# Nuio_LeftKeyboard_Rev_E_2_MCU.net
KiCad netlist of a schematic drawn in Altium Designer
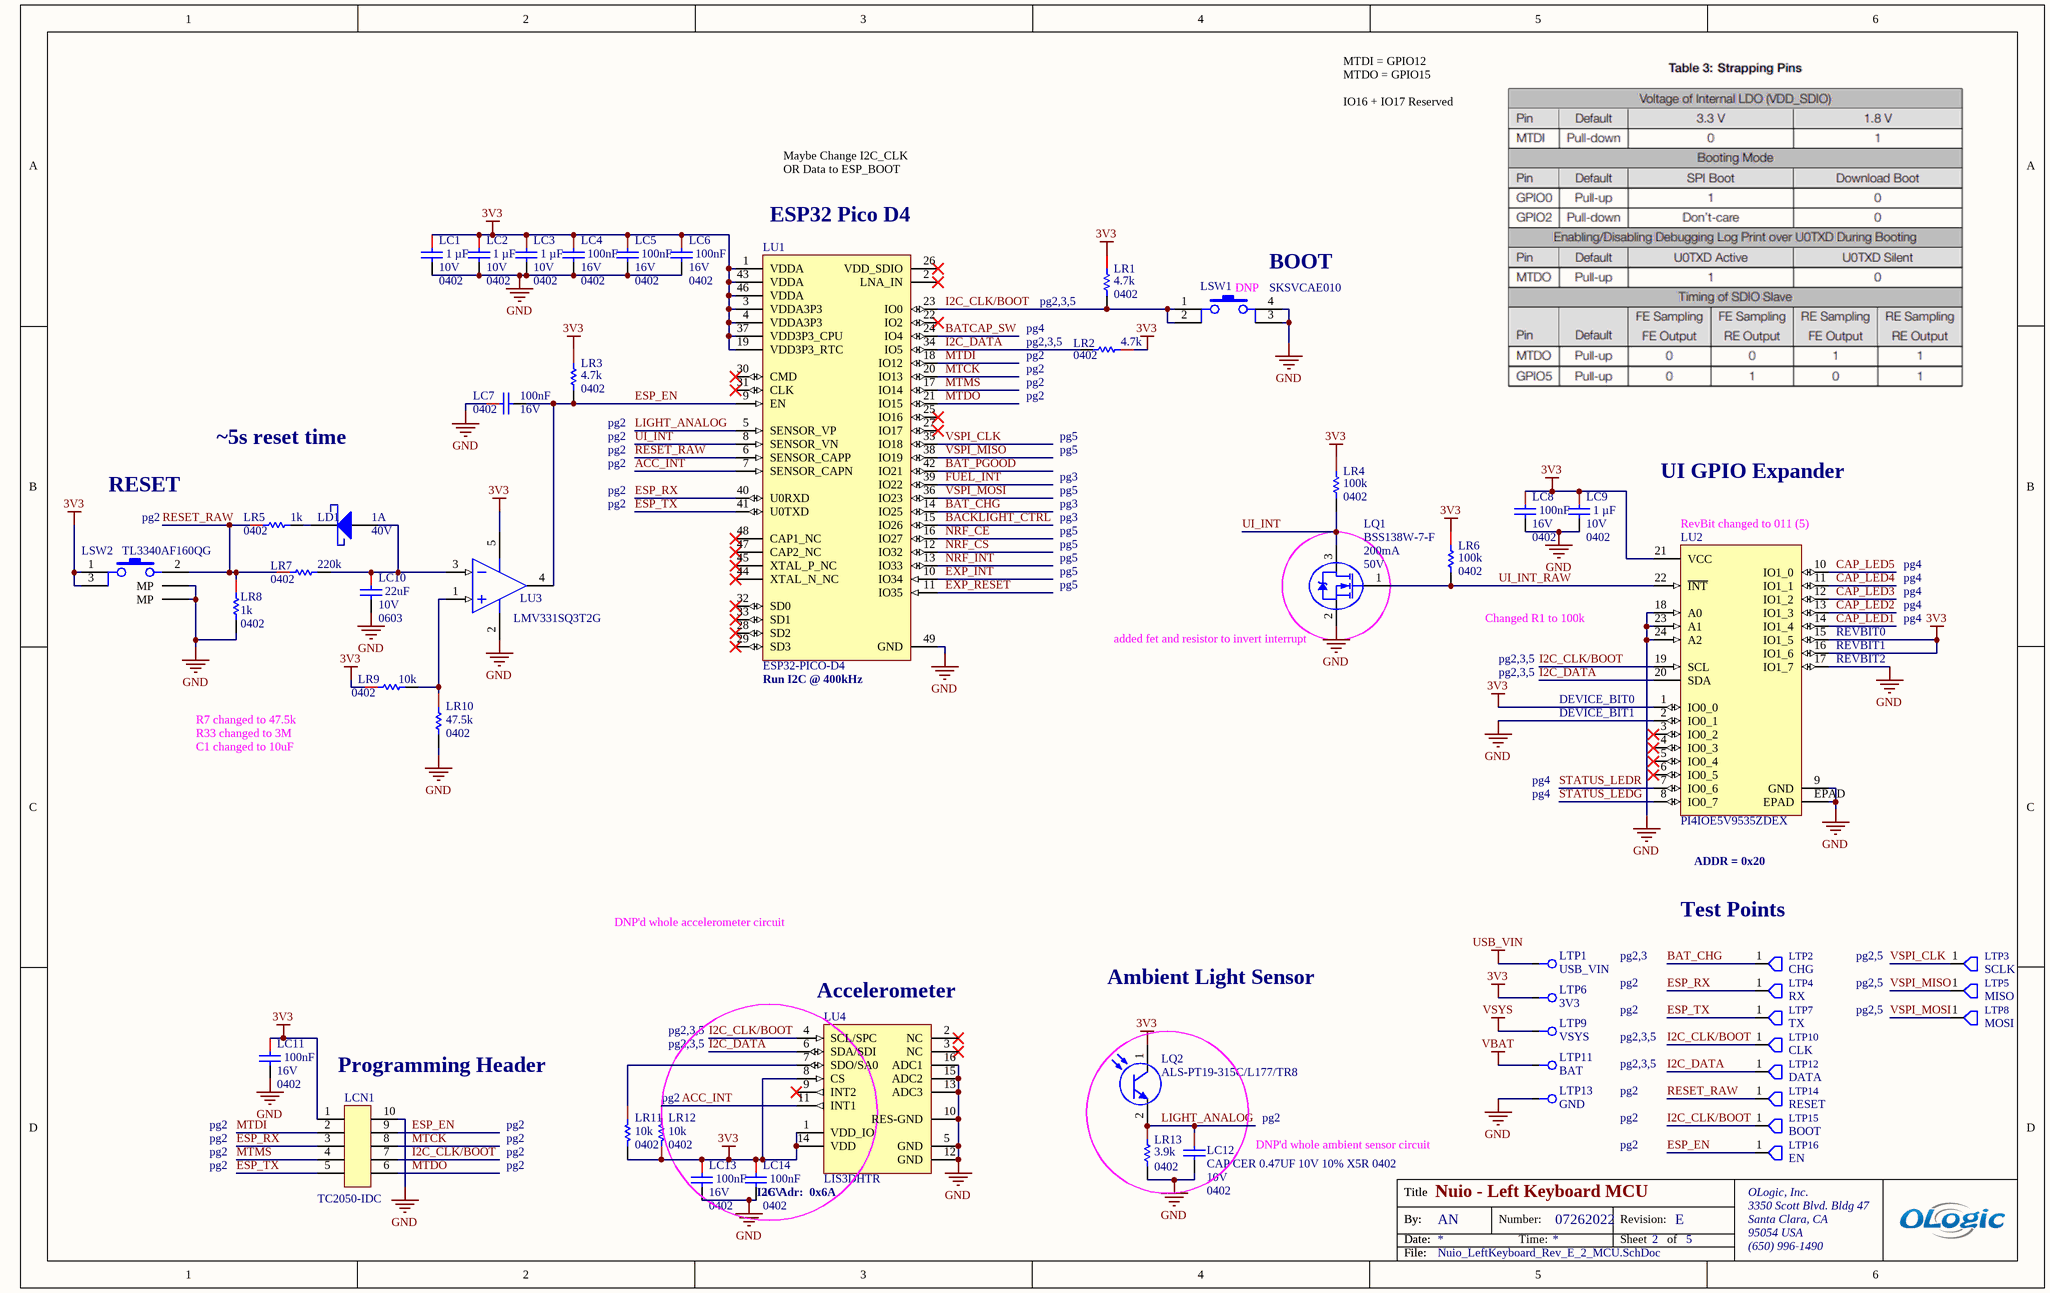
[diagram p0: Nuio_LeftKeyboard_Rev_E_2_MCU.SchDoc]

(export (version "E")
  (design (tool "Eeschema 10.0.6"))
  (components
    (comp (ref "LC1")
      (value "CAP CER 1UF 10V X5R 0402")
      (footprint "CAPC0402(1005)_L")
      (description "±20% 10V Ceramic Capacitor X5R 0402 (1005 Metric)")
      (fields
        (field (name "PACKAGE (IMPERIAL)") "0402")
        (field (name "VOLTAGE (RATED)") "10V")
        (field (name "CAPACITANCE") "1 µF")
        (field (name "MANUFACTURER PART NUMBER") "CC0402MRX5R6BB105")
        (field (name "TOLERANCE") "±20%")
      )
      (libsource (lib "OLogic Nexus Vault") (part "OL_Capacitor"))
    )
    (comp (ref "LC2")
      (value "CAP CER 1UF 10V X5R 0402")
      (footprint "CAPC0402(1005)_L")
      (description "±20% 10V Ceramic Capacitor X5R 0402 (1005 Metric)")
      (fields
        (field (name "PACKAGE (IMPERIAL)") "0402")
        (field (name "VOLTAGE (RATED)") "10V")
        (field (name "CAPACITANCE") "1 µF")
        (field (name "MANUFACTURER PART NUMBER") "CC0402MRX5R6BB105")
        (field (name "TOLERANCE") "±20%")
      )
      (libsource (lib "OLogic Nexus Vault") (part "OL_Capacitor"))
    )
    (comp (ref "LC3")
      (value "CAP CER 1UF 10V X5R 0402")
      (footprint "CAPC0402(1005)_L")
      (description "±20% 10V Ceramic Capacitor X5R 0402 (1005 Metric)")
      (fields
        (field (name "PACKAGE (IMPERIAL)") "0402")
        (field (name "VOLTAGE (RATED)") "10V")
        (field (name "CAPACITANCE") "1 µF")
        (field (name "MANUFACTURER PART NUMBER") "CC0402MRX5R6BB105")
        (field (name "TOLERANCE") "±20%")
      )
      (libsource (lib "OLogic Nexus Vault") (part "OL_Capacitor"))
    )
    (comp (ref "LC4")
      (value "CAP CER 0.1UF 16V X5R 0402")
      (footprint "CAPC0402(1005)_L")
      (description "±10% 16V Ceramic Capacitor X5R 0402 (1005 Metric)")
      (fields
        (field (name "PACKAGE (IMPERIAL)") "0402")
        (field (name "VOLTAGE (RATED)") "16V")
        (field (name "CAPACITANCE") "100nF")
        (field (name "MANUFACTURER") "Taiyo Yuden")
        (field (name "MANUFACTURER PART NUMBER") "EMK105BJ104KV-F")
      )
      (libsource (lib "OLogic Nexus Vault") (part "OL_Capacitor"))
    )
    (comp (ref "LC5")
      (value "CAP CER 0.1UF 16V X5R 0402")
      (footprint "CAPC0402(1005)_L")
      (description "±10% 16V Ceramic Capacitor X5R 0402 (1005 Metric)")
      (fields
        (field (name "PACKAGE (IMPERIAL)") "0402")
        (field (name "VOLTAGE (RATED)") "16V")
        (field (name "CAPACITANCE") "100nF")
        (field (name "MANUFACTURER") "Taiyo Yuden")
        (field (name "MANUFACTURER PART NUMBER") "EMK105BJ104KV-F")
      )
      (libsource (lib "OLogic Nexus Vault") (part "OL_Capacitor"))
    )
    (comp (ref "LC6")
      (value "CAP CER 0.1UF 16V X5R 0402")
      (footprint "CAPC0402(1005)_L")
      (description "±10% 16V Ceramic Capacitor X5R 0402 (1005 Metric)")
      (fields
        (field (name "PACKAGE (IMPERIAL)") "0402")
        (field (name "VOLTAGE (RATED)") "16V")
        (field (name "CAPACITANCE") "100nF")
        (field (name "MANUFACTURER") "Taiyo Yuden")
        (field (name "MANUFACTURER PART NUMBER") "EMK105BJ104KV-F")
      )
      (libsource (lib "OLogic Nexus Vault") (part "OL_Capacitor"))
    )
    (comp (ref "LC7")
      (value "CAP CER 0.1UF 16V X5R 0402")
      (footprint "CAPC0402(1005)_L")
      (description "±10% 16V Ceramic Capacitor X5R 0402 (1005 Metric)")
      (fields
        (field (name "PACKAGE (IMPERIAL)") "0402")
        (field (name "VOLTAGE (RATED)") "16V")
        (field (name "CAPACITANCE") "100nF")
        (field (name "MANUFACTURER") "Taiyo Yuden")
        (field (name "MANUFACTURER PART NUMBER") "EMK105BJ104KV-F")
      )
      (libsource (lib "OLogic Nexus Vault") (part "OL_Capacitor"))
    )
    (comp (ref "LC8")
      (value "CAP CER 0.1UF 16V X5R 0402")
      (footprint "CAPC0402(1005)_L")
      (description "±10% 16V Ceramic Capacitor X5R 0402 (1005 Metric)")
      (fields
        (field (name "PACKAGE (IMPERIAL)") "0402")
        (field (name "VOLTAGE (RATED)") "16V")
        (field (name "CAPACITANCE") "100nF")
        (field (name "MANUFACTURER") "Taiyo Yuden")
        (field (name "MANUFACTURER PART NUMBER") "EMK105BJ104KV-F")
      )
      (libsource (lib "OLogic Nexus Vault") (part "OL_Capacitor"))
    )
    (comp (ref "LC9")
      (value "CAP CER 1UF 10V X5R 0402")
      (footprint "CAPC0402(1005)_L")
      (description "±20% 10V Ceramic Capacitor X5R 0402 (1005 Metric)")
      (fields
        (field (name "PACKAGE (IMPERIAL)") "0402")
        (field (name "VOLTAGE (RATED)") "10V")
        (field (name "CAPACITANCE") "1 µF")
        (field (name "MANUFACTURER PART NUMBER") "CC0402MRX5R6BB105")
        (field (name "TOLERANCE") "±20%")
      )
      (libsource (lib "OLogic Nexus Vault") (part "OL_Capacitor"))
    )
    (comp (ref "LC10")
      (value "22uF")
      (footprint "CAPC0603(1608)_L")
      (description "CAP CER 22UF 10V 20% 0603")
      (fields
        (field (name "VOLTAGE RATING (DC)") "10V")
        (field (name "CASE CODE (IMPERIAL)") "0603")
        (field (name "TOLERANCE") "20%")
      )
      (libsource (lib "OLogic Nexus Vault") (part "=Capacitance"))
    )
    (comp (ref "LC11")
      (value "CAP CER 0.1UF 16V X5R 0402")
      (footprint "CAPC0402(1005)_L")
      (description "±10% 16V Ceramic Capacitor X5R 0402 (1005 Metric)")
      (fields
        (field (name "PACKAGE (IMPERIAL)") "0402")
        (field (name "VOLTAGE (RATED)") "16V")
        (field (name "CAPACITANCE") "100nF")
        (field (name "MANUFACTURER") "Taiyo Yuden")
        (field (name "MANUFACTURER PART NUMBER") "EMK105BJ104KV-F")
      )
      (libsource (lib "OLogic Nexus Vault") (part "OL_Capacitor"))
    )
    (comp (ref "LC12")
      (value "CAP CER 0.47UF 10V 10% X5R 0402")
      (footprint "CAPC0402(1005)_L")
      (description "0.47 µF ±10% 10V Ceramic Capacitor X7S 0402 (1005 Metric)")
      (fields
        (field (name "VOLTAGE (RATED)") "10V")
        (field (name "PACKAGE (IMPERIAL)") "0402")
        (field (name "TOLERANCE") "10%")
      )
      (libsource (lib "OLogic Nexus Vault") (part "OL_Capacitor"))
    )
    (comp (ref "LC13")
      (value "CAP CER 0.1UF 16V X5R 0402")
      (footprint "CAPC0402(1005)_L")
      (description "±10% 16V Ceramic Capacitor X5R 0402 (1005 Metric)")
      (fields
        (field (name "PACKAGE (IMPERIAL)") "0402")
        (field (name "VOLTAGE (RATED)") "16V")
        (field (name "CAPACITANCE") "100nF")
        (field (name "MANUFACTURER") "Taiyo Yuden")
        (field (name "MANUFACTURER PART NUMBER") "EMK105BJ104KV-F")
      )
      (libsource (lib "OLogic Nexus Vault") (part "OL_Capacitor"))
    )
    (comp (ref "LC14")
      (value "CAP CER 0.1UF 16V X5R 0402")
      (footprint "CAPC0402(1005)_L")
      (description "±10% 16V Ceramic Capacitor X5R 0402 (1005 Metric)")
      (fields
        (field (name "PACKAGE (IMPERIAL)") "0402")
        (field (name "VOLTAGE (RATED)") "16V")
        (field (name "CAPACITANCE") "100nF")
        (field (name "MANUFACTURER") "Taiyo Yuden")
        (field (name "MANUFACTURER PART NUMBER") "EMK105BJ104KV-F")
      )
      (libsource (lib "OLogic Nexus Vault") (part "OL_Capacitor"))
    )
    (comp (ref "LCN1")
      (value "TC2050-IDC")
      (footprint "TC2050-IDC")
      (description "Adapter Cbl Plug Of Nails 10PIN")
      (libsource (lib "OLogic Nexus Vault") (part "TC2050-IDC"))
    )
    (comp (ref "LD1")
      (value "PMEG4010AESBYL")
      (footprint "PMEG4010AESBYL-Footprint-1")
      (description "DIODE SCHOTTKY 40V 1A SOD993")
      (fields (field (name "DC REVERSE VOLTAGE MAX") "40V") (field (name "CURRENT AVG RECTIFIED") "1A"))
      (libsource (lib "OLogic Nexus Vault") (part "PMEG4010AESB"))
    )
    (comp (ref "LQ1")
      (value "BSS138W-7-F")
      (footprint "DIOD-SOT323-3_V")
      (description "DIODES INC. - BSS138W-7-F. - BSS FAMILY SOT323 T&R 3K ROHS COMPLIANT: YES")
      (fields
        (field (name "VOLTAGE") "50V")
        (field (name "POWER") "200mW")
        (field (name "CONTINUOUS DRAIN CURRENT (ID)") "200mA")
        (field (name "VOLTAGE RATING (DC)") "50V")
      )
      (libsource (lib "OLogic Nexus Vault") (part "OL_NFET_GSD"))
    )
    (comp (ref "LQ2")
      (value "ALS-PT19-315C/L177/TR8")
      (footprint "ALS-PT19-315C_L177_TR8")
      (description "SENSOR PHOTO 630NM 2SMD")
      (fields (field (name "MANUFACTURER") "Everlight Electronics Co Ltd"))
      (libsource (lib "OLogic Nexus Vault") (part "ALS-PT19-315C_L177_TR8"))
    )
    (comp (ref "LR1")
      (value "4.7k")
      (footprint "RESC0402(1005)_L")
      (description "4.7 kOhms ±1% 0.063W, 1/16W Chip Resistor 0402 (1005 Metric) Moisture Resistant Thick Film")
      (fields
        (field (name "TOLERANCE") "1%")
        (field (name "CASE/PACKAGE") "0402")
        (field (name "MANUFACTURER") "YAGEO")
      )
      (libsource (lib "OLogic Nexus Vault") (part "=Resistance"))
    )
    (comp (ref "LR2")
      (value "4.7k")
      (footprint "RESC0402(1005)_L")
      (description "4.7 kOhms ±1% 0.063W, 1/16W Chip Resistor 0402 (1005 Metric) Moisture Resistant Thick Film")
      (fields
        (field (name "TOLERANCE") "1%")
        (field (name "CASE CODE (IMPERIAL)") "0402")
        (field (name "MANUFACTURER") "YAGEO")
      )
      (libsource (lib "OLogic Nexus Vault") (part "=Resistance"))
    )
    (comp (ref "LR3")
      (value "4.7k")
      (footprint "RESC0402(1005)_L")
      (description "4.7 kOhms ±1% 0.063W, 1/16W Chip Resistor 0402 (1005 Metric) Moisture Resistant Thick Film")
      (fields
        (field (name "TOLERANCE") "1%")
        (field (name "CASE CODE (IMPERIAL)") "0402")
        (field (name "MANUFACTURER") "YAGEO")
      )
      (libsource (lib "OLogic Nexus Vault") (part "=Resistance"))
    )
    (comp (ref "LR4")
      (value "100k")
      (footprint "RESC0402(1005)_L")
      (description "±1% 0.063W, 1/16W Chip Resistor 0402 (1005 Metric) Moisture Resistant Thick Film")
      (fields
        (field (name "CASE CODE (IMPERIAL)") "0402")
        (field (name "TOLERANCE") "1%")
        (field (name "MANUFACTURER") "YAGEO")
      )
      (libsource (lib "OLogic Nexus Vault") (part "=Resistance"))
    )
    (comp (ref "LR5")
      (value "RES SMD 1K OHM 1% 1/16W 0402")
      (footprint "RESC0402(1005)_L")
      (fields
        (field (name "RESISTANCE") "1k")
        (field (name "PACKAGE (IMPERIAL)") "0402")
        (field (name "POWER") "63mW")
        (field (name "MANUFACTURER") "Yageo")
        (field (name "TOLERANCE") "1%")
      )
      (libsource (lib "OLogic Nexus Vault") (part "OL_Resistor"))
    )
    (comp (ref "LR6")
      (value "100k")
      (footprint "RESC0402(1005)_L")
      (description "±1% 0.063W, 1/16W Chip Resistor 0402 (1005 Metric) Moisture Resistant Thick Film")
      (fields
        (field (name "CASE CODE (IMPERIAL)") "0402")
        (field (name "TOLERANCE") "1%")
        (field (name "MANUFACTURER") "YAGEO")
      )
      (libsource (lib "OLogic Nexus Vault") (part "=Resistance"))
    )
    (comp (ref "LR7")
      (value "220K")
      (footprint "RESC0402(1005)_L")
      (description "RES SMD 220K OHM 1% 1/10W 0402")
      (fields
        (field (name "PACKAGE (IMPERIAL)") "0402")
        (field (name "RESISTANCE") "220k")
        (field (name "TOLERANCE") "1%")
        (field (name "POWER") "63mW")
      )
      (libsource (lib "OLogic Nexus Vault") (part "=Resistance"))
    )
    (comp (ref "LR8")
      (value "RES SMD 1K OHM 1% 1/16W 0402")
      (footprint "RESC0402(1005)_L")
      (fields
        (field (name "RESISTANCE") "1k")
        (field (name "PACKAGE (IMPERIAL)") "0402")
        (field (name "POWER") "63mW")
        (field (name "MANUFACTURER") "Yageo")
        (field (name "TOLERANCE") "1%")
      )
      (libsource (lib "OLogic Nexus Vault") (part "OL_Resistor"))
    )
    (comp (ref "LR9")
      (value "RES SMD 10K OHM 1% 1/16W 0402")
      (footprint "RESC0402_YAGEO")
      (fields
        (field (name "RESISTANCE") "10k")
        (field (name "PACKAGE (IMPERIAL)") "0402")
        (field (name "MANUFACTURER") "Yageo")
        (field (name "TOLERANCE") "1%")
        (field (name "MANUFACTURER PART NUMBER") "AT0402FRE0710KL")
      )
      (libsource (lib "OLogic Nexus Vault") (part "OL_Resistor"))
    )
    (comp (ref "LR10")
      (value "RES 47.5K OHM 1% 1/16W 0402")
      (footprint "RESC0402(1005)_L")
      (description "47.5 kOhms ±1% 0.063W, 1/16W Chip Resistor 0402 (1005 Metric) Moisture Resistant Thick Film")
      (fields
        (field (name "RESISTANCE") "47.5k")
        (field (name "PACKAGE (IMPERIAL)") "0402")
        (field (name "MANUFACTURER") "Panasonic Electronic Components")
        (field (name "MANUFACTURER PART NUMBER") "ERA-2ARB6041X")
      )
      (libsource (lib "OLogic Nexus Vault") (part "OL_Resistor"))
    )
    (comp (ref "LR11")
      (value "RES SMD 10K OHM 1% 1/16W 0402")
      (footprint "RESC0402(1005)_L")
      (description "10 kOhms ±1% 0.063W, 1/16W Chip Resistor 0402 (1005 Metric) Thin Film")
      (fields
        (field (name "PACKAGE (IMPERIAL)") "0402")
        (field (name "RESISTANCE") "10k")
        (field (name "POWER") "63mW")
        (field (name "TOLERANCE") "1%")
      )
      (libsource (lib "OLogic Nexus Vault") (part "=Resistance"))
    )
    (comp (ref "LR12")
      (value "RES SMD 10K OHM 1% 1/16W 0402")
      (footprint "RESC0402(1005)_L")
      (description "10 kOhms ±1% 0.063W, 1/16W Chip Resistor 0402 (1005 Metric) Thin Film")
      (fields
        (field (name "PACKAGE (IMPERIAL)") "0402")
        (field (name "RESISTANCE") "10k")
        (field (name "POWER") "63mW")
        (field (name "TOLERANCE") "1%")
      )
      (libsource (lib "OLogic Nexus Vault") (part "=Resistance"))
    )
    (comp (ref "LR13")
      (value "3.9K")
      (footprint "RESC0402(1005)_L")
      (description "RES 3.9K OHM 1% 1/16W 0402")
      (fields
        (field (name "PACKAGE (IMPERIAL)") "0402")
        (field (name "POWER") "63mW")
        (field (name "RESISTANCE") "3.9k")
        (field (name "TOLERANCE") "1%")
      )
      (libsource (lib "OLogic Nexus Vault") (part "=Resistance"))
    )
    (comp (ref "LSW1")
      (value "SKSVCAE010")
      (footprint "SKSVCAE010")
      (description "2.8x1.9mm Compact Type with Projection Surface Mount SKSV Series Tact Switch")
      (fields (field (name "MANUFACTURER") "Alps Alpine"))
      (libsource (lib "OLogic Nexus Vault") (part "OL_Switch_Tactile_4"))
    )
    (comp (ref "LSW2")
      (value "TL3340AF160QG")
      (footprint "TL3340AF160QG")
      (description "SWITCH TACTILE SPST-NO 0.05A 12V")
      (libsource (lib "OLogic Nexus Vault") (part "TL3340AF160QG"))
    )
    (comp (ref "LTP1")
      (value "USB_VIN")
      (footprint "Pogo-Testpoint")
      (description "Test Point- Current one")
      (libsource (lib "OLogic Nexus Vault") (part "TestPoint"))
    )
    (comp (ref "LTP2")
      (value "CHG")
      (footprint "MTK-TESTPOINT-20")
      (description "MTK-TP20MIL")
      (libsource (lib "OLogic Nexus Vault") (part "MTK-TESTPOINT-20"))
    )
    (comp (ref "LTP3")
      (value "SCLK")
      (footprint "MTK-TESTPOINT-20")
      (description "MTK-TP20MIL")
      (libsource (lib "OLogic Nexus Vault") (part "MTK-TESTPOINT-20"))
    )
    (comp (ref "LTP4")
      (value "RX")
      (footprint "MTK-TESTPOINT-20")
      (description "MTK-TP20MIL")
      (libsource (lib "OLogic Nexus Vault") (part "MTK-TESTPOINT-20"))
    )
    (comp (ref "LTP5")
      (value "MISO")
      (footprint "MTK-TESTPOINT-20")
      (description "MTK-TP20MIL")
      (libsource (lib "OLogic Nexus Vault") (part "MTK-TESTPOINT-20"))
    )
    (comp (ref "LTP6")
      (value "3V3")
      (footprint "Pogo-Testpoint")
      (description "Test Point- Current one")
      (libsource (lib "OLogic Nexus Vault") (part "TestPoint"))
    )
    (comp (ref "LTP7")
      (value "TX")
      (footprint "MTK-TESTPOINT-20")
      (description "MTK-TP20MIL")
      (libsource (lib "OLogic Nexus Vault") (part "MTK-TESTPOINT-20"))
    )
    (comp (ref "LTP8")
      (value "MOSI")
      (footprint "MTK-TESTPOINT-20")
      (description "MTK-TP20MIL")
      (libsource (lib "OLogic Nexus Vault") (part "MTK-TESTPOINT-20"))
    )
    (comp (ref "LTP9")
      (value "VSYS")
      (footprint "Pogo-Testpoint")
      (description "Test Point- Current one")
      (libsource (lib "OLogic Nexus Vault") (part "TestPoint"))
    )
    (comp (ref "LTP10")
      (value "CLK")
      (footprint "MTK-TESTPOINT-20")
      (description "MTK-TP20MIL")
      (libsource (lib "OLogic Nexus Vault") (part "MTK-TESTPOINT-20"))
    )
    (comp (ref "LTP11")
      (value "BAT")
      (footprint "Pogo-Testpoint")
      (description "Test Point- Current one")
      (libsource (lib "OLogic Nexus Vault") (part "TestPoint"))
    )
    (comp (ref "LTP12")
      (value "DATA")
      (footprint "MTK-TESTPOINT-20")
      (description "MTK-TP20MIL")
      (libsource (lib "OLogic Nexus Vault") (part "MTK-TESTPOINT-20"))
    )
    (comp (ref "LTP13")
      (value "GND")
      (footprint "Pogo-Testpoint")
      (description "Test Point- Current one")
      (libsource (lib "OLogic Nexus Vault") (part "TestPoint"))
    )
    (comp (ref "LTP14")
      (value "RESET")
      (footprint "MTK-TESTPOINT-20")
      (description "MTK-TP20MIL")
      (libsource (lib "OLogic Nexus Vault") (part "MTK-TESTPOINT-20"))
    )
    (comp (ref "LTP15")
      (value "BOOT")
      (footprint "MTK-TESTPOINT-20")
      (description "MTK-TP20MIL")
      (libsource (lib "OLogic Nexus Vault") (part "MTK-TESTPOINT-20"))
    )
    (comp (ref "LTP16")
      (value "EN")
      (footprint "MTK-TESTPOINT-20")
      (description "MTK-TP20MIL")
      (libsource (lib "OLogic Nexus Vault") (part "MTK-TESTPOINT-20"))
    )
    (comp (ref "LU1")
      (value "ESP32-PICO-D4")
      (footprint "ESP32-PICO-D4")
      (description "Rx Txrx Mod Wifi Surface Mount")
      (fields (field (name "MANUFACTURER") "Espressif Systems"))
      (libsource (lib "OLogic Nexus Vault") (part "ESP32-PICO-D4"))
    )
    (comp (ref "LU2")
      (value "PI4IOE5V9535ZDEX")
      (footprint "PI4IOE5V9535ZDEX")
      (description "I/O Expander 16 I²C 400 kHz 24-TQFN (4x4)")
      (libsource (lib "OLogic Nexus Vault") (part "PI4IOE5V9535ZDEX"))
    )
    (comp (ref "LU3")
      (value "LMV331SQ3T2G")
      (footprint "ONSC-SC70-5-419A-02_K_L")
      (description "LMV Series 5 V 1 nA SMT Single General Purpose, Low Voltage Comparator - SC-70")
      (fields (field (name "MANUFACTURER") "onsemi"))
      (libsource (lib "OLogic Nexus Vault") (part "ONSC-LMV331-5"))
    )
    (comp (ref "LU4")
      (value "LIS3DHTR")
      (footprint "LGA16")
      (description "3-Axis Accelerometer")
      (fields (field (name "MANUFACTURER") "STMicro") (field (name "MPN") "LIS3DSH"))
      (libsource (lib "OLogic Nexus Vault") (part "LIS3DHTR"))
    )
  )
  (nets
    (net (code "1") (name "/ACC_INT") (class "Default")
      (node (ref "LR12") (pin "2") (pinfunction "2_2") (pintype "passive"))
      (node (ref "LU1") (pin "7") (pinfunction "SENSOR_CAPN_7") (pintype "input"))
      (node (ref "LU4") (pin "11") (pinfunction "INT1_11") (pintype "output"))
    )
    (net (code "2") (name "/BACKLIGHT_CTRL") (class "Default")
      (node (ref "LU1") (pin "15") (pinfunction "IO26_15") (pintype "bidirectional"))
    )
    (net (code "3") (name "/BATCAP_SW") (class "Default")
      (node (ref "LU1") (pin "24") (pinfunction "IO4_24") (pintype "bidirectional"))
    )
    (net (code "4") (name "/BAT_CHG") (class "Default")
      (node (ref "LTP2") (pin "1") (pinfunction "TP_1") (pintype "passive"))
      (node (ref "LU1") (pin "14") (pinfunction "IO25_14") (pintype "bidirectional"))
    )
    (net (code "5") (name "/BAT_PGOOD") (class "Default")
      (node (ref "LU1") (pin "42") (pinfunction "IO21_42") (pintype "bidirectional"))
    )
    (net (code "6") (name "/CAP_LED1") (class "Default")
      (node (ref "LU2") (pin "14") (pinfunction "IO1_4_14") (pintype "bidirectional"))
    )
    (net (code "7") (name "/CAP_LED2") (class "Default")
      (node (ref "LU2") (pin "13") (pinfunction "IO1_3_13") (pintype "bidirectional"))
    )
    (net (code "8") (name "/CAP_LED3") (class "Default")
      (node (ref "LU2") (pin "12") (pinfunction "IO1_2_12") (pintype "bidirectional"))
    )
    (net (code "9") (name "/CAP_LED4") (class "Default")
      (node (ref "LU2") (pin "11") (pinfunction "IO1_1_11") (pintype "bidirectional"))
    )
    (net (code "10") (name "/CAP_LED5") (class "Default")
      (node (ref "LU2") (pin "10") (pinfunction "IO1_0_10") (pintype "bidirectional"))
    )
    (net (code "11") (name "/ESP_EN") (class "Default")
      (node (ref "LC7") (pin "2") (pinfunction "2_2") (pintype "passive"))
      (node (ref "LCN1") (pin "9") (pintype "passive"))
      (node (ref "LR3") (pin "2") (pinfunction "2_2") (pintype "passive"))
      (node (ref "LTP16") (pin "1") (pinfunction "TP_1") (pintype "passive"))
      (node (ref "LU1") (pin "9") (pinfunction "EN_9") (pintype "input"))
      (node (ref "LU3") (pin "4") (pinfunction "OUT_4") (pintype "open_collector"))
    )
    (net (code "12") (name "/ESP_RX") (class "Default")
      (node (ref "LCN1") (pin "3") (pintype "passive"))
      (node (ref "LTP4") (pin "1") (pinfunction "TP_1") (pintype "passive"))
      (node (ref "LU1") (pin "40") (pinfunction "U0RXD_40") (pintype "bidirectional"))
    )
    (net (code "13") (name "/ESP_TX") (class "Default")
      (node (ref "LCN1") (pin "5") (pintype "passive"))
      (node (ref "LTP7") (pin "1") (pinfunction "TP_1") (pintype "passive"))
      (node (ref "LU1") (pin "41") (pinfunction "U0TXD_41") (pintype "bidirectional"))
    )
    (net (code "14") (name "/EXP_INT") (class "Default")
      (node (ref "LU1") (pin "10") (pinfunction "IO34_10") (pintype "input"))
    )
    (net (code "15") (name "/EXP_RESET") (class "Default")
      (node (ref "LU1") (pin "11") (pinfunction "IO35_11") (pintype "input"))
    )
    (net (code "16") (name "/FUEL_INT") (class "Default")
      (node (ref "LU1") (pin "39") (pinfunction "IO22_39") (pintype "bidirectional"))
    )
    (net (code "17") (name "/I2C_CLK{slash}BOOT") (class "Default")
      (node (ref "LCN1") (pin "7") (pintype "passive"))
      (node (ref "LR1") (pin "2") (pinfunction "2_2") (pintype "passive"))
      (node (ref "LSW1") (pin "1") (pinfunction "1_1") (pintype "passive"))
      (node (ref "LSW1") (pin "2") (pinfunction "2_2") (pintype "passive"))
      (node (ref "LTP10") (pin "1") (pinfunction "TP_1") (pintype "passive"))
      (node (ref "LTP15") (pin "1") (pinfunction "TP_1") (pintype "passive"))
      (node (ref "LU1") (pin "23") (pinfunction "IO0_23") (pintype "bidirectional"))
      (node (ref "LU2") (pin "19") (pinfunction "SCL_19") (pintype "input"))
      (node (ref "LU4") (pin "4") (pinfunction "SCL/SPC_4") (pintype "input"))
    )
    (net (code "18") (name "/I2C_DATA") (class "Default")
      (node (ref "LR2") (pin "2") (pinfunction "2_2") (pintype "passive"))
      (node (ref "LTP12") (pin "1") (pinfunction "TP_1") (pintype "passive"))
      (node (ref "LU1") (pin "34") (pinfunction "IO5_34") (pintype "bidirectional"))
      (node (ref "LU2") (pin "20") (pinfunction "SDA_20") (pintype "passive"))
      (node (ref "LU4") (pin "6") (pinfunction "SDA/SDI_6") (pintype "bidirectional"))
    )
    (net (code "19") (name "/LIGHT_ANALOG") (class "Default")
      (node (ref "LC12") (pin "1") (pinfunction "1_1") (pintype "passive"))
      (node (ref "LQ2") (pin "2") (pinfunction "E_2") (pintype "passive"))
      (node (ref "LR13") (pin "1") (pinfunction "1_1") (pintype "passive"))
      (node (ref "LU1") (pin "5") (pinfunction "SENSOR_VP_5") (pintype "input"))
    )
    (net (code "20") (name "/MTCK") (class "Default")
      (node (ref "LCN1") (pin "8") (pintype "passive"))
      (node (ref "LU1") (pin "20") (pinfunction "IO13_20") (pintype "bidirectional"))
    )
    (net (code "21") (name "/MTDI") (class "Default")
      (node (ref "LCN1") (pin "2") (pintype "passive"))
      (node (ref "LU1") (pin "18") (pinfunction "IO12_18") (pintype "bidirectional"))
    )
    (net (code "22") (name "/MTDO") (class "Default")
      (node (ref "LCN1") (pin "6") (pintype "passive"))
      (node (ref "LU1") (pin "21") (pinfunction "IO15_21") (pintype "bidirectional"))
    )
    (net (code "23") (name "/MTMS") (class "Default")
      (node (ref "LCN1") (pin "4") (pintype "passive"))
      (node (ref "LU1") (pin "17") (pinfunction "IO14_17") (pintype "bidirectional"))
    )
    (net (code "24") (name "/NRF_CE") (class "Default")
      (node (ref "LU1") (pin "16") (pinfunction "IO27_16") (pintype "bidirectional"))
    )
    (net (code "25") (name "/NRF_CS") (class "Default")
      (node (ref "LU1") (pin "12") (pinfunction "IO32_12") (pintype "bidirectional"))
    )
    (net (code "26") (name "/NRF_INT") (class "Default")
      (node (ref "LU1") (pin "13") (pinfunction "IO33_13") (pintype "bidirectional"))
    )
    (net (code "27") (name "/RESET_RAW") (class "Default")
      (node (ref "LR5") (pin "1") (pinfunction "1_1") (pintype "passive"))
      (node (ref "LR7") (pin "1") (pinfunction "1_1") (pintype "passive"))
      (node (ref "LR8") (pin "1") (pinfunction "1_1") (pintype "passive"))
      (node (ref "LSW2") (pin "2") (pinfunction "2_2") (pintype "passive"))
      (node (ref "LTP14") (pin "1") (pinfunction "TP_1") (pintype "passive"))
      (node (ref "LU1") (pin "6") (pinfunction "SENSOR_CAPP_6") (pintype "input"))
    )
    (net (code "28") (name "/STATUS_LEDG") (class "Default")
      (node (ref "LU2") (pin "8") (pinfunction "IO0_7_8") (pintype "bidirectional"))
    )
    (net (code "29") (name "/STATUS_LEDR") (class "Default")
      (node (ref "LU2") (pin "7") (pinfunction "IO0_6_7") (pintype "bidirectional"))
    )
    (net (code "30") (name "/UI_INT") (class "Default")
      (node (ref "LQ1") (pin "3") (pinfunction "D_3") (pintype "passive"))
      (node (ref "LR4") (pin "2") (pinfunction "2_2") (pintype "passive"))
      (node (ref "LU1") (pin "8") (pinfunction "SENSOR_VN_8") (pintype "input"))
    )
    (net (code "31") (name "/UI_INT_RAW") (class "Default")
      (node (ref "LQ1") (pin "1") (pinfunction "G_1") (pintype "passive"))
      (node (ref "LR6") (pin "2") (pinfunction "2_2") (pintype "passive"))
      (node (ref "LU2") (pin "22") (pinfunction "~{INT}_22") (pintype "input"))
    )
    (net (code "32") (name "/VSPI_CLK") (class "Default")
      (node (ref "LTP3") (pin "1") (pinfunction "TP_1") (pintype "passive"))
      (node (ref "LU1") (pin "35") (pinfunction "IO18_35") (pintype "bidirectional"))
    )
    (net (code "33") (name "/VSPI_MISO") (class "Default")
      (node (ref "LTP5") (pin "1") (pinfunction "TP_1") (pintype "passive"))
      (node (ref "LU1") (pin "38") (pinfunction "IO19_38") (pintype "bidirectional"))
    )
    (net (code "34") (name "/VSPI_MOSI") (class "Default")
      (node (ref "LTP8") (pin "1") (pinfunction "TP_1") (pintype "passive"))
      (node (ref "LU1") (pin "36") (pinfunction "IO23_36") (pintype "bidirectional"))
    )
    (net (code "35") (name "3V3") (class "Default")
      (node (ref "LC1") (pin "1") (pinfunction "1_1") (pintype "passive"))
      (node (ref "LC11") (pin "1") (pinfunction "1_1") (pintype "passive"))
      (node (ref "LC13") (pin "1") (pinfunction "1_1") (pintype "passive"))
      (node (ref "LC14") (pin "1") (pinfunction "1_1") (pintype "passive"))
      (node (ref "LC2") (pin "1") (pinfunction "1_1") (pintype "passive"))
      (node (ref "LC3") (pin "1") (pinfunction "1_1") (pintype "passive"))
      (node (ref "LC4") (pin "1") (pinfunction "1_1") (pintype "passive"))
      (node (ref "LC5") (pin "1") (pinfunction "1_1") (pintype "passive"))
      (node (ref "LC6") (pin "1") (pinfunction "1_1") (pintype "passive"))
      (node (ref "LC8") (pin "1") (pinfunction "1_1") (pintype "passive"))
      (node (ref "LC9") (pin "1") (pinfunction "1_1") (pintype "passive"))
      (node (ref "LCN1") (pin "1") (pintype "passive"))
      (node (ref "LQ2") (pin "1") (pinfunction "C_1") (pintype "passive"))
      (node (ref "LR1") (pin "1") (pinfunction "1_1") (pintype "passive"))
      (node (ref "LR11") (pin "2") (pinfunction "2_2") (pintype "passive"))
      (node (ref "LR12") (pin "1") (pinfunction "1_1") (pintype "passive"))
      (node (ref "LR2") (pin "1") (pinfunction "1_1") (pintype "passive"))
      (node (ref "LR3") (pin "1") (pinfunction "1_1") (pintype "passive"))
      (node (ref "LR4") (pin "1") (pinfunction "1_1") (pintype "passive"))
      (node (ref "LR6") (pin "1") (pinfunction "1_1") (pintype "passive"))
      (node (ref "LR9") (pin "1") (pinfunction "1_1") (pintype "passive"))
      (node (ref "LSW2") (pin "1") (pinfunction "1_1") (pintype "passive"))
      (node (ref "LSW2") (pin "3") (pinfunction "3_3") (pintype "passive"))
      (node (ref "LTP6") (pin "1") (pinfunction "1_1") (pintype "passive"))
      (node (ref "LU1") (pin "1") (pinfunction "VDDA_1") (pintype "power_in"))
      (node (ref "LU1") (pin "19") (pinfunction "VDD3P3_RTC_19") (pintype "passive"))
      (node (ref "LU1") (pin "3") (pinfunction "VDDA3P3_3") (pintype "power_in"))
      (node (ref "LU1") (pin "37") (pinfunction "VDD3P3_CPU_37") (pintype "power_in"))
      (node (ref "LU1") (pin "4") (pinfunction "VDDA3P3_4") (pintype "power_in"))
      (node (ref "LU1") (pin "43") (pinfunction "VDDA_43") (pintype "power_in"))
      (node (ref "LU1") (pin "46") (pinfunction "VDDA_46") (pintype "power_in"))
      (node (ref "LU2") (pin "1") (pinfunction "IO0_0_1") (pintype "bidirectional"))
      (node (ref "LU2") (pin "15") (pinfunction "IO1_5_15") (pintype "bidirectional"))
      (node (ref "LU2") (pin "16") (pinfunction "IO1_6_16") (pintype "bidirectional"))
      (node (ref "LU2") (pin "21") (pinfunction "VCC_21") (pintype "power_in"))
      (node (ref "LU3") (pin "5") (pinfunction "VCC_5") (pintype "power_in"))
      (node (ref "LU4") (pin "1") (pinfunction "VDD_IO_1") (pintype "power_in"))
      (node (ref "LU4") (pin "14") (pinfunction "VDD_14") (pintype "power_in"))
      (node (ref "LU4") (pin "8") (pinfunction "CS_8") (pintype "input"))
    )
    (net (code "36") (name "GND") (class "Default")
      (node (ref "LC1") (pin "2") (pinfunction "2_2") (pintype "passive"))
      (node (ref "LC10") (pin "2") (pinfunction "2_2") (pintype "passive"))
      (node (ref "LC11") (pin "2") (pinfunction "2_2") (pintype "passive"))
      (node (ref "LC12") (pin "2") (pinfunction "2_2") (pintype "passive"))
      (node (ref "LC13") (pin "2") (pinfunction "2_2") (pintype "passive"))
      (node (ref "LC14") (pin "2") (pinfunction "2_2") (pintype "passive"))
      (node (ref "LC2") (pin "2") (pinfunction "2_2") (pintype "passive"))
      (node (ref "LC3") (pin "2") (pinfunction "2_2") (pintype "passive"))
      (node (ref "LC4") (pin "2") (pinfunction "2_2") (pintype "passive"))
      (node (ref "LC5") (pin "2") (pinfunction "2_2") (pintype "passive"))
      (node (ref "LC6") (pin "2") (pinfunction "2_2") (pintype "passive"))
      (node (ref "LC7") (pin "1") (pinfunction "1_1") (pintype "passive"))
      (node (ref "LC8") (pin "2") (pinfunction "2_2") (pintype "passive"))
      (node (ref "LC9") (pin "2") (pinfunction "2_2") (pintype "passive"))
      (node (ref "LCN1") (pin "10") (pintype "passive"))
      (node (ref "LQ1") (pin "2") (pinfunction "S_2") (pintype "passive"))
      (node (ref "LR10") (pin "2") (pinfunction "2_2") (pintype "passive"))
      (node (ref "LR13") (pin "2") (pinfunction "2_2") (pintype "passive"))
      (node (ref "LR8") (pin "2") (pinfunction "2_2") (pintype "passive"))
      (node (ref "LSW1") (pin "3") (pinfunction "3_3") (pintype "passive"))
      (node (ref "LSW1") (pin "4") (pinfunction "4_4") (pintype "passive"))
      (node (ref "LSW2") (pin "MP1") (pinfunction "MP_MP1") (pintype "passive"))
      (node (ref "LSW2") (pin "MP2") (pinfunction "MP_MP2") (pintype "passive"))
      (node (ref "LTP13") (pin "1") (pinfunction "1_1") (pintype "passive"))
      (node (ref "LU1") (pin "49") (pinfunction "GND_49") (pintype "power_in"))
      (node (ref "LU2") (pin "17") (pinfunction "IO1_7_17") (pintype "bidirectional"))
      (node (ref "LU2") (pin "18") (pinfunction "A0_18") (pintype "input"))
      (node (ref "LU2") (pin "2") (pinfunction "IO0_1_2") (pintype "bidirectional"))
      (node (ref "LU2") (pin "23") (pinfunction "A1_23") (pintype "input"))
      (node (ref "LU2") (pin "24") (pinfunction "A2_24") (pintype "input"))
      (node (ref "LU2") (pin "9") (pinfunction "GND_9") (pintype "power_in"))
      (node (ref "LU2") (pin "EPAD") (pinfunction "EPAD_EPAD") (pintype "power_in"))
      (node (ref "LU3") (pin "2") (pinfunction "GND_2") (pintype "power_in"))
      (node (ref "LU4") (pin "10") (pinfunction "RES-GND_10") (pintype "passive"))
      (node (ref "LU4") (pin "12") (pinfunction "GND_12") (pintype "power_in"))
      (node (ref "LU4") (pin "13") (pinfunction "ADC3_13") (pintype "passive"))
      (node (ref "LU4") (pin "15") (pinfunction "ADC2_15") (pintype "passive"))
      (node (ref "LU4") (pin "16") (pinfunction "ADC1_16") (pintype "power_in"))
      (node (ref "LU4") (pin "5") (pinfunction "GND_5") (pintype "power_in"))
    )
    (net (code "37") (name "Net-(LD1-A)") (class "Default")
      (node (ref "LC10") (pin "1") (pinfunction "1_1") (pintype "passive"))
      (node (ref "LD1") (pin "2") (pinfunction "A_2") (pintype "passive"))
      (node (ref "LR7") (pin "2") (pinfunction "2_2") (pintype "passive"))
      (node (ref "LU3") (pin "3") (pinfunction "IN-_3") (pintype "input"))
    )
    (net (code "38") (name "Net-(LD1-K)") (class "Default")
      (node (ref "LD1") (pin "1") (pinfunction "K_1") (pintype "passive"))
      (node (ref "LR5") (pin "2") (pinfunction "2_2") (pintype "passive"))
    )
    (net (code "39") (name "Net-(LU3-IN+)") (class "Default")
      (node (ref "LR10") (pin "1") (pinfunction "1_1") (pintype "passive"))
      (node (ref "LR9") (pin "2") (pinfunction "2_2") (pintype "passive"))
      (node (ref "LU3") (pin "1") (pinfunction "IN+_1") (pintype "input"))
    )
    (net (code "40") (name "Net-(LU4-SDO{slash}SA0)") (class "Default")
      (node (ref "LR11") (pin "1") (pinfunction "1_1") (pintype "passive"))
      (node (ref "LU4") (pin "7") (pinfunction "SDO/SA0_7") (pintype "bidirectional"))
    )
    (net (code "41") (name "USB_VIN") (class "Default")
      (node (ref "LTP1") (pin "1") (pinfunction "1_1") (pintype "passive"))
    )
    (net (code "42") (name "VBAT") (class "Default")
      (node (ref "LTP11") (pin "1") (pinfunction "1_1") (pintype "passive"))
    )
    (net (code "43") (name "VSYS") (class "Default")
      (node (ref "LTP9") (pin "1") (pinfunction "1_1") (pintype "passive"))
    )
    (net (code "44") (name "unconnected-(LU1-CAP1_NC-Pad48)") (class "Default")
      (node (ref "LU1") (pin "48") (pinfunction "CAP1_NC_48") (pintype "passive+no_connect"))
    )
    (net (code "45") (name "unconnected-(LU1-CAP2_NC-Pad47)") (class "Default")
      (node (ref "LU1") (pin "47") (pinfunction "CAP2_NC_47") (pintype "passive+no_connect"))
    )
    (net (code "46") (name "unconnected-(LU1-CLK-Pad31)") (class "Default")
      (node (ref "LU1") (pin "31") (pinfunction "CLK_31") (pintype "bidirectional+no_connect"))
    )
    (net (code "47") (name "unconnected-(LU1-CMD-Pad30)") (class "Default")
      (node (ref "LU1") (pin "30") (pinfunction "CMD_30") (pintype "bidirectional+no_connect"))
    )
    (net (code "48") (name "unconnected-(LU1-IO2-Pad22)") (class "Default")
      (node (ref "LU1") (pin "22") (pinfunction "IO2_22") (pintype "bidirectional+no_connect"))
    )
    (net (code "49") (name "unconnected-(LU1-IO16-Pad25)") (class "Default")
      (node (ref "LU1") (pin "25") (pinfunction "IO16_25") (pintype "bidirectional+no_connect"))
    )
    (net (code "50") (name "unconnected-(LU1-IO17-Pad27)") (class "Default")
      (node (ref "LU1") (pin "27") (pinfunction "IO17_27") (pintype "bidirectional+no_connect"))
    )
    (net (code "51") (name "unconnected-(LU1-LNA_IN-Pad2)") (class "Default")
      (node (ref "LU1") (pin "2") (pinfunction "LNA_IN_2") (pintype "passive+no_connect"))
    )
    (net (code "52") (name "unconnected-(LU1-SD0-Pad32)") (class "Default")
      (node (ref "LU1") (pin "32") (pinfunction "SD0_32") (pintype "bidirectional+no_connect"))
    )
    (net (code "53") (name "unconnected-(LU1-SD1-Pad33)") (class "Default")
      (node (ref "LU1") (pin "33") (pinfunction "SD1_33") (pintype "bidirectional+no_connect"))
    )
    (net (code "54") (name "unconnected-(LU1-SD2-Pad28)") (class "Default")
      (node (ref "LU1") (pin "28") (pinfunction "SD2_28") (pintype "bidirectional+no_connect"))
    )
    (net (code "55") (name "unconnected-(LU1-SD3-Pad29)") (class "Default")
      (node (ref "LU1") (pin "29") (pinfunction "SD3_29") (pintype "bidirectional+no_connect"))
    )
    (net (code "56") (name "unconnected-(LU1-VDD_SDIO-Pad26)") (class "Default")
      (node (ref "LU1") (pin "26") (pinfunction "VDD_SDIO_26") (pintype "power_in+no_connect"))
    )
    (net (code "57") (name "unconnected-(LU1-XTAL_N_NC-Pad44)") (class "Default")
      (node (ref "LU1") (pin "44") (pinfunction "XTAL_N_NC_44") (pintype "passive+no_connect"))
    )
    (net (code "58") (name "unconnected-(LU1-XTAL_P_NC-Pad45)") (class "Default")
      (node (ref "LU1") (pin "45") (pinfunction "XTAL_P_NC_45") (pintype "passive+no_connect"))
    )
    (net (code "59") (name "unconnected-(LU2-IO0_2-Pad3)") (class "Default")
      (node (ref "LU2") (pin "3") (pinfunction "IO0_2_3") (pintype "bidirectional+no_connect"))
    )
    (net (code "60") (name "unconnected-(LU2-IO0_3-Pad4)") (class "Default")
      (node (ref "LU2") (pin "4") (pinfunction "IO0_3_4") (pintype "bidirectional+no_connect"))
    )
    (net (code "61") (name "unconnected-(LU2-IO0_4-Pad5)") (class "Default")
      (node (ref "LU2") (pin "5") (pinfunction "IO0_4_5") (pintype "bidirectional+no_connect"))
    )
    (net (code "62") (name "unconnected-(LU2-IO0_5-Pad6)") (class "Default")
      (node (ref "LU2") (pin "6") (pinfunction "IO0_5_6") (pintype "bidirectional+no_connect"))
    )
    (net (code "63") (name "unconnected-(LU4-INT2-Pad9)") (class "Default")
      (node (ref "LU4") (pin "9") (pinfunction "INT2_9") (pintype "output+no_connect"))
    )
    (net (code "64") (name "unconnected-(LU4-NC-Pad2)") (class "Default")
      (node (ref "LU4") (pin "2") (pinfunction "NC_2") (pintype "power_in+no_connect"))
    )
    (net (code "65") (name "unconnected-(LU4-NC-Pad3)") (class "Default")
      (node (ref "LU4") (pin "3") (pinfunction "NC_3") (pintype "passive+no_connect"))
    )
  )
)
